# interconnect-board.net
KiCad netlist of a schematic drawn in EAGLE
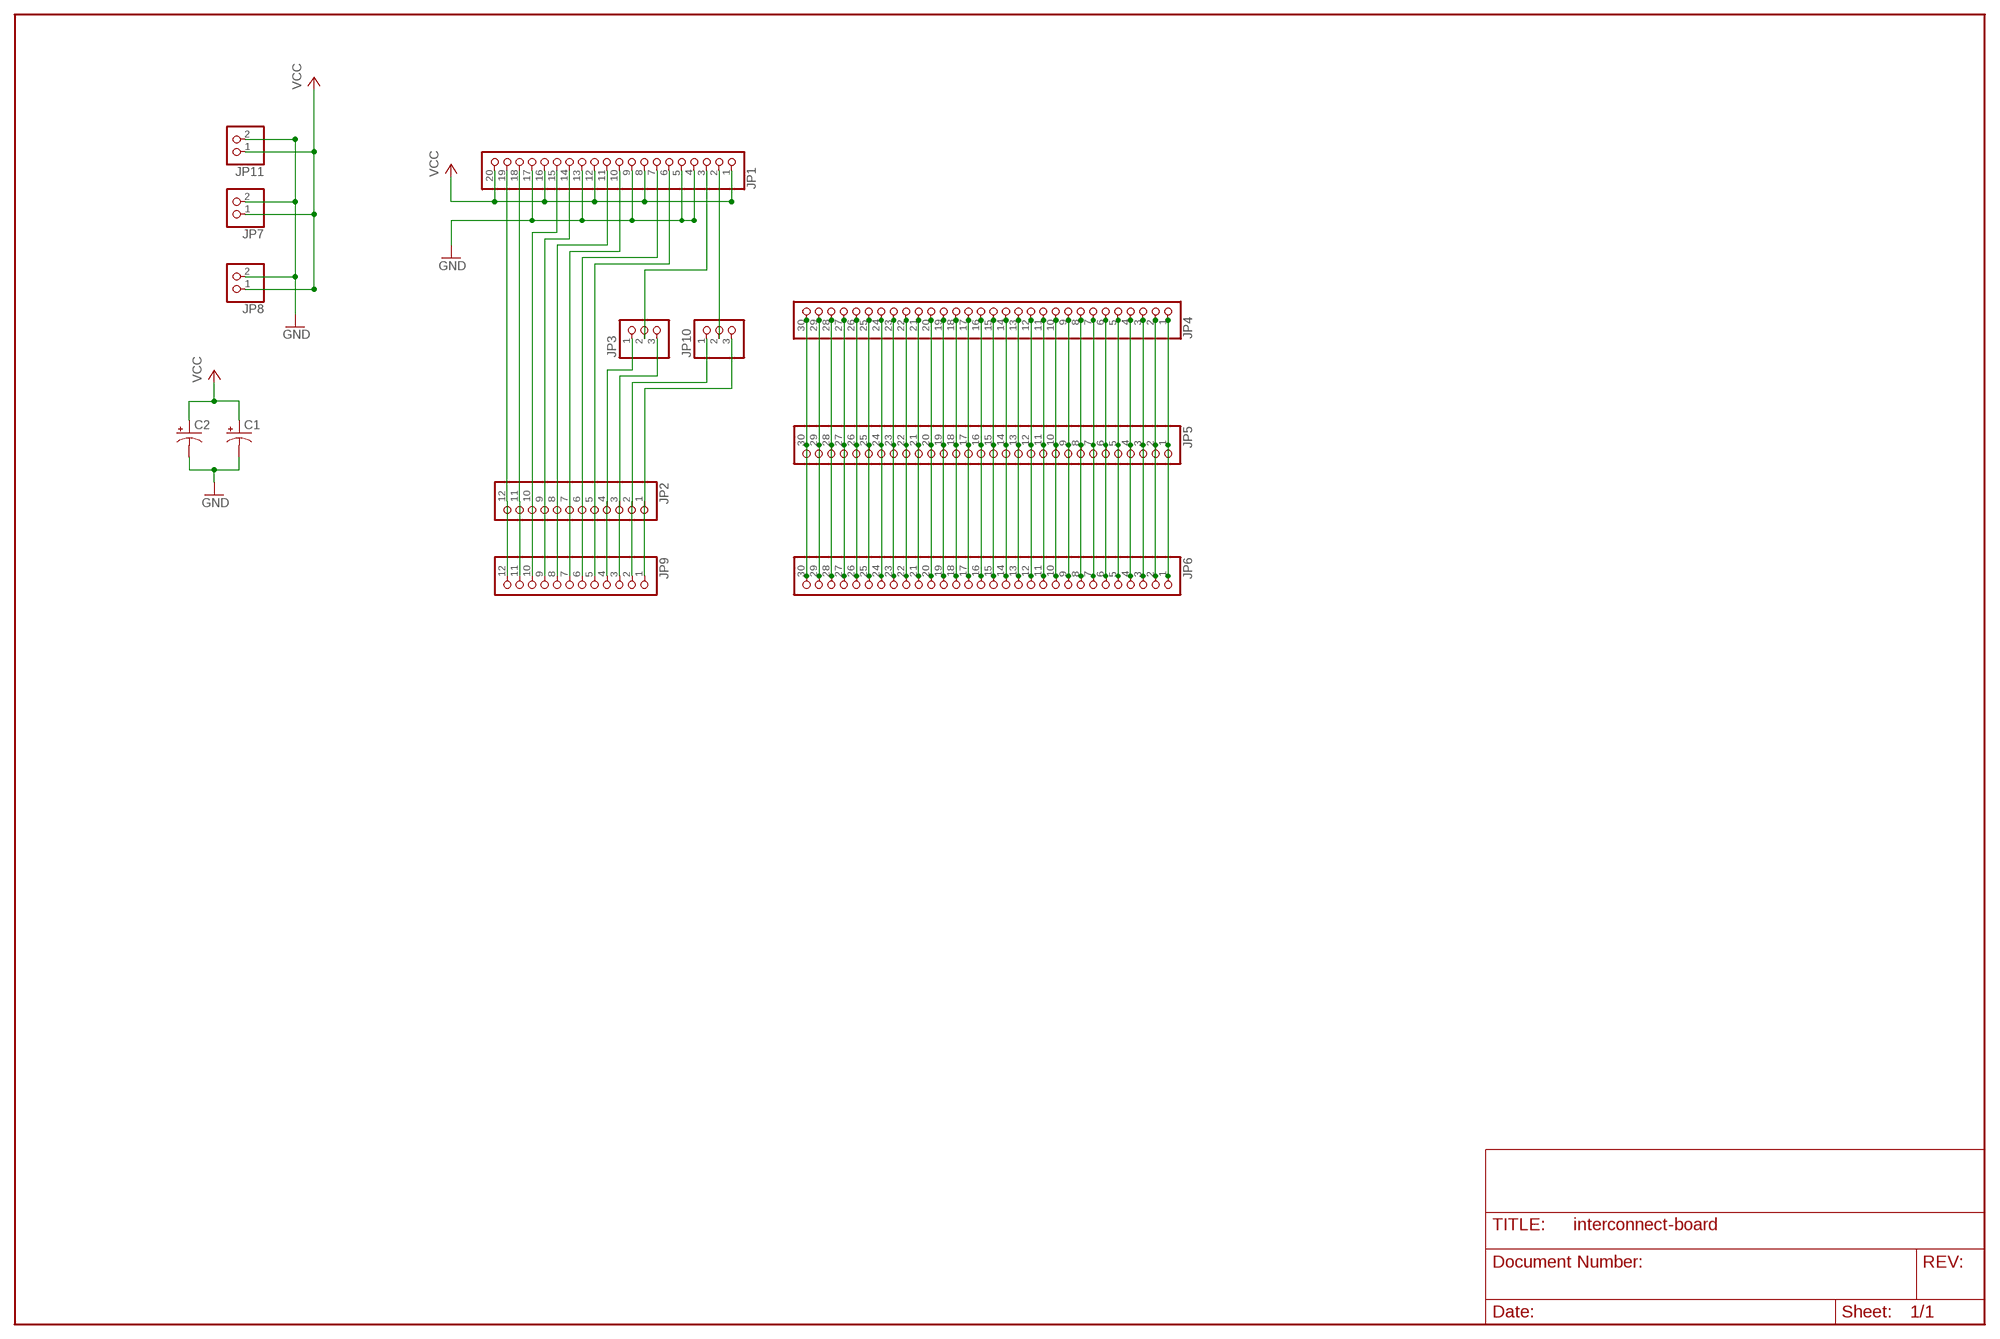
[diagram p0: schematic, sheet 1]

(export (version "E")
  (design (tool "Eeschema 10.0.6"))
  (components
    (comp (ref "C1")
      (value "CPOL-USE15-6AXIAL")
      (footprint "eagle-import:E15-6")
      (libsource (lib "eagle-import") (part "CPOL-USE15-6AXIAL"))
    )
    (comp (ref "C2")
      (value "CPOL-USE15-6AXIAL")
      (footprint "eagle-import:E15-6")
      (libsource (lib "eagle-import") (part "CPOL-USE15-6AXIAL"))
    )
    (comp (ref "JP1")
      (value "PINHD-1X20")
      (footprint "eagle-import:1X20")
      (libsource (lib "eagle-import") (part "PINHD-1X20"))
    )
    (comp (ref "JP2")
      (value "PINHD-1X12")
      (footprint "eagle-import:1X12")
      (libsource (lib "eagle-import") (part "PINHD-1X12"))
    )
    (comp (ref "JP3")
      (value "PINHD-1X3")
      (footprint "eagle-import:1X03")
      (libsource (lib "eagle-import") (part "PINHD-1X3"))
    )
    (comp (ref "JP4")
      (value "PINHD-1X30")
      (footprint "eagle-import:1X30")
      (libsource (lib "eagle-import") (part "PINHD-1X30"))
    )
    (comp (ref "JP5")
      (value "PINHD-1X30")
      (footprint "eagle-import:1X30")
      (libsource (lib "eagle-import") (part "PINHD-1X30"))
    )
    (comp (ref "JP6")
      (value "PINHD-1X30")
      (footprint "eagle-import:1X30")
      (libsource (lib "eagle-import") (part "PINHD-1X30"))
    )
    (comp (ref "JP7")
      (value "PINHD-1X2")
      (footprint "eagle-import:1X02")
      (libsource (lib "eagle-import") (part "PINHD-1X2"))
    )
    (comp (ref "JP8")
      (value "PINHD-1X2")
      (footprint "eagle-import:1X02")
      (libsource (lib "eagle-import") (part "PINHD-1X2"))
    )
    (comp (ref "JP9")
      (value "PINHD-1X12")
      (footprint "eagle-import:1X12")
      (libsource (lib "eagle-import") (part "PINHD-1X12"))
    )
    (comp (ref "JP10")
      (value "PINHD-1X3")
      (footprint "eagle-import:1X03")
      (libsource (lib "eagle-import") (part "PINHD-1X3"))
    )
    (comp (ref "JP11")
      (value "PINHD-1X2")
      (footprint "eagle-import:1X02")
      (libsource (lib "eagle-import") (part "PINHD-1X2"))
    )
  )
  (nets
    (net (code "1") (name "GND") (class "Default")
      (node (ref "C1") (pin "-") (pinfunction "-_-") (pintype "passive"))
      (node (ref "C2") (pin "-") (pinfunction "-_-") (pintype "passive"))
      (node (ref "JP1") (pin "13") (pinfunction "13_13") (pintype "passive"))
      (node (ref "JP1") (pin "17") (pinfunction "17_17") (pintype "passive"))
      (node (ref "JP1") (pin "4") (pinfunction "4_4") (pintype "passive"))
      (node (ref "JP1") (pin "5") (pinfunction "5_5") (pintype "passive"))
      (node (ref "JP1") (pin "9") (pinfunction "9_9") (pintype "passive"))
      (node (ref "JP11") (pin "2") (pinfunction "2_2") (pintype "passive"))
      (node (ref "JP7") (pin "2") (pinfunction "2_2") (pintype "passive"))
      (node (ref "JP8") (pin "2") (pinfunction "2_2") (pintype "passive"))
    )
    (net (code "2") (name "Net-(JP1-Pad2)") (class "Default")
      (node (ref "JP1") (pin "2") (pinfunction "2_2") (pintype "passive"))
      (node (ref "JP10") (pin "2") (pinfunction "2_2") (pintype "passive"))
    )
    (net (code "3") (name "Net-(JP1-Pad3)") (class "Default")
      (node (ref "JP1") (pin "3") (pinfunction "3_3") (pintype "passive"))
      (node (ref "JP3") (pin "2") (pinfunction "2_2") (pintype "passive"))
    )
    (net (code "4") (name "Net-(JP1-Pad6)") (class "Default")
      (node (ref "JP1") (pin "6") (pinfunction "6_6") (pintype "passive"))
      (node (ref "JP2") (pin "5") (pinfunction "5_5") (pintype "passive"))
      (node (ref "JP9") (pin "5") (pinfunction "5_5") (pintype "passive"))
    )
    (net (code "5") (name "Net-(JP1-Pad7)") (class "Default")
      (node (ref "JP1") (pin "7") (pinfunction "7_7") (pintype "passive"))
      (node (ref "JP2") (pin "6") (pinfunction "6_6") (pintype "passive"))
      (node (ref "JP9") (pin "6") (pinfunction "6_6") (pintype "passive"))
    )
    (net (code "6") (name "Net-(JP1-Pad10)") (class "Default")
      (node (ref "JP1") (pin "10") (pinfunction "10_10") (pintype "passive"))
      (node (ref "JP2") (pin "7") (pinfunction "7_7") (pintype "passive"))
      (node (ref "JP9") (pin "7") (pinfunction "7_7") (pintype "passive"))
    )
    (net (code "7") (name "Net-(JP1-Pad11)") (class "Default")
      (node (ref "JP1") (pin "11") (pinfunction "11_11") (pintype "passive"))
      (node (ref "JP2") (pin "8") (pinfunction "8_8") (pintype "passive"))
      (node (ref "JP9") (pin "8") (pinfunction "8_8") (pintype "passive"))
    )
    (net (code "8") (name "Net-(JP1-Pad14)") (class "Default")
      (node (ref "JP1") (pin "14") (pinfunction "14_14") (pintype "passive"))
      (node (ref "JP2") (pin "9") (pinfunction "9_9") (pintype "passive"))
      (node (ref "JP9") (pin "9") (pinfunction "9_9") (pintype "passive"))
    )
    (net (code "9") (name "Net-(JP1-Pad15)") (class "Default")
      (node (ref "JP1") (pin "15") (pinfunction "15_15") (pintype "passive"))
      (node (ref "JP2") (pin "10") (pinfunction "10_10") (pintype "passive"))
      (node (ref "JP9") (pin "10") (pinfunction "10_10") (pintype "passive"))
    )
    (net (code "10") (name "Net-(JP1-Pad18)") (class "Default")
      (node (ref "JP1") (pin "18") (pinfunction "18_18") (pintype "passive"))
      (node (ref "JP2") (pin "11") (pinfunction "11_11") (pintype "passive"))
      (node (ref "JP9") (pin "11") (pinfunction "11_11") (pintype "passive"))
    )
    (net (code "11") (name "Net-(JP1-Pad19)") (class "Default")
      (node (ref "JP1") (pin "19") (pinfunction "19_19") (pintype "passive"))
      (node (ref "JP2") (pin "12") (pinfunction "12_12") (pintype "passive"))
      (node (ref "JP9") (pin "12") (pinfunction "12_12") (pintype "passive"))
    )
    (net (code "12") (name "Net-(JP2-Pad3)") (class "Default")
      (node (ref "JP2") (pin "3") (pinfunction "3_3") (pintype "passive"))
      (node (ref "JP3") (pin "3") (pinfunction "3_3") (pintype "passive"))
      (node (ref "JP9") (pin "3") (pinfunction "3_3") (pintype "passive"))
    )
    (net (code "13") (name "Net-(JP2-Pad4)") (class "Default")
      (node (ref "JP2") (pin "4") (pinfunction "4_4") (pintype "passive"))
      (node (ref "JP3") (pin "1") (pinfunction "1_1") (pintype "passive"))
      (node (ref "JP9") (pin "4") (pinfunction "4_4") (pintype "passive"))
    )
    (net (code "14") (name "Net-(JP4-Pad1)") (class "Default")
      (node (ref "JP4") (pin "1") (pinfunction "1_1") (pintype "passive"))
      (node (ref "JP5") (pin "1") (pinfunction "1_1") (pintype "passive"))
      (node (ref "JP6") (pin "1") (pinfunction "1_1") (pintype "passive"))
    )
    (net (code "15") (name "Net-(JP4-Pad2)") (class "Default")
      (node (ref "JP4") (pin "2") (pinfunction "2_2") (pintype "passive"))
      (node (ref "JP5") (pin "2") (pinfunction "2_2") (pintype "passive"))
      (node (ref "JP6") (pin "2") (pinfunction "2_2") (pintype "passive"))
    )
    (net (code "16") (name "Net-(JP4-Pad3)") (class "Default")
      (node (ref "JP4") (pin "3") (pinfunction "3_3") (pintype "passive"))
      (node (ref "JP5") (pin "3") (pinfunction "3_3") (pintype "passive"))
      (node (ref "JP6") (pin "3") (pinfunction "3_3") (pintype "passive"))
    )
    (net (code "17") (name "Net-(JP4-Pad4)") (class "Default")
      (node (ref "JP4") (pin "4") (pinfunction "4_4") (pintype "passive"))
      (node (ref "JP5") (pin "4") (pinfunction "4_4") (pintype "passive"))
      (node (ref "JP6") (pin "4") (pinfunction "4_4") (pintype "passive"))
    )
    (net (code "18") (name "Net-(JP4-Pad5)") (class "Default")
      (node (ref "JP4") (pin "5") (pinfunction "5_5") (pintype "passive"))
      (node (ref "JP5") (pin "5") (pinfunction "5_5") (pintype "passive"))
      (node (ref "JP6") (pin "5") (pinfunction "5_5") (pintype "passive"))
    )
    (net (code "19") (name "Net-(JP4-Pad6)") (class "Default")
      (node (ref "JP4") (pin "6") (pinfunction "6_6") (pintype "passive"))
      (node (ref "JP5") (pin "6") (pinfunction "6_6") (pintype "passive"))
      (node (ref "JP6") (pin "6") (pinfunction "6_6") (pintype "passive"))
    )
    (net (code "20") (name "Net-(JP4-Pad7)") (class "Default")
      (node (ref "JP4") (pin "7") (pinfunction "7_7") (pintype "passive"))
      (node (ref "JP5") (pin "7") (pinfunction "7_7") (pintype "passive"))
      (node (ref "JP6") (pin "7") (pinfunction "7_7") (pintype "passive"))
    )
    (net (code "21") (name "Net-(JP4-Pad8)") (class "Default")
      (node (ref "JP4") (pin "8") (pinfunction "8_8") (pintype "passive"))
      (node (ref "JP5") (pin "8") (pinfunction "8_8") (pintype "passive"))
      (node (ref "JP6") (pin "8") (pinfunction "8_8") (pintype "passive"))
    )
    (net (code "22") (name "Net-(JP4-Pad9)") (class "Default")
      (node (ref "JP4") (pin "9") (pinfunction "9_9") (pintype "passive"))
      (node (ref "JP5") (pin "9") (pinfunction "9_9") (pintype "passive"))
      (node (ref "JP6") (pin "9") (pinfunction "9_9") (pintype "passive"))
    )
    (net (code "23") (name "Net-(JP4-Pad10)") (class "Default")
      (node (ref "JP4") (pin "10") (pinfunction "10_10") (pintype "passive"))
      (node (ref "JP5") (pin "10") (pinfunction "10_10") (pintype "passive"))
      (node (ref "JP6") (pin "10") (pinfunction "10_10") (pintype "passive"))
    )
    (net (code "24") (name "Net-(JP4-Pad11)") (class "Default")
      (node (ref "JP4") (pin "11") (pinfunction "11_11") (pintype "passive"))
      (node (ref "JP5") (pin "11") (pinfunction "11_11") (pintype "passive"))
      (node (ref "JP6") (pin "11") (pinfunction "11_11") (pintype "passive"))
    )
    (net (code "25") (name "Net-(JP4-Pad12)") (class "Default")
      (node (ref "JP4") (pin "12") (pinfunction "12_12") (pintype "passive"))
      (node (ref "JP5") (pin "12") (pinfunction "12_12") (pintype "passive"))
      (node (ref "JP6") (pin "12") (pinfunction "12_12") (pintype "passive"))
    )
    (net (code "26") (name "Net-(JP4-Pad13)") (class "Default")
      (node (ref "JP4") (pin "13") (pinfunction "13_13") (pintype "passive"))
      (node (ref "JP5") (pin "13") (pinfunction "13_13") (pintype "passive"))
      (node (ref "JP6") (pin "13") (pinfunction "13_13") (pintype "passive"))
    )
    (net (code "27") (name "Net-(JP4-Pad14)") (class "Default")
      (node (ref "JP4") (pin "14") (pinfunction "14_14") (pintype "passive"))
      (node (ref "JP5") (pin "14") (pinfunction "14_14") (pintype "passive"))
      (node (ref "JP6") (pin "14") (pinfunction "14_14") (pintype "passive"))
    )
    (net (code "28") (name "Net-(JP4-Pad15)") (class "Default")
      (node (ref "JP4") (pin "15") (pinfunction "15_15") (pintype "passive"))
      (node (ref "JP5") (pin "15") (pinfunction "15_15") (pintype "passive"))
      (node (ref "JP6") (pin "15") (pinfunction "15_15") (pintype "passive"))
    )
    (net (code "29") (name "Net-(JP4-Pad16)") (class "Default")
      (node (ref "JP4") (pin "16") (pinfunction "16_16") (pintype "passive"))
      (node (ref "JP5") (pin "16") (pinfunction "16_16") (pintype "passive"))
      (node (ref "JP6") (pin "16") (pinfunction "16_16") (pintype "passive"))
    )
    (net (code "30") (name "Net-(JP4-Pad17)") (class "Default")
      (node (ref "JP4") (pin "17") (pinfunction "17_17") (pintype "passive"))
      (node (ref "JP5") (pin "17") (pinfunction "17_17") (pintype "passive"))
      (node (ref "JP6") (pin "17") (pinfunction "17_17") (pintype "passive"))
    )
    (net (code "31") (name "Net-(JP4-Pad18)") (class "Default")
      (node (ref "JP4") (pin "18") (pinfunction "18_18") (pintype "passive"))
      (node (ref "JP5") (pin "18") (pinfunction "18_18") (pintype "passive"))
      (node (ref "JP6") (pin "18") (pinfunction "18_18") (pintype "passive"))
    )
    (net (code "32") (name "Net-(JP4-Pad19)") (class "Default")
      (node (ref "JP4") (pin "19") (pinfunction "19_19") (pintype "passive"))
      (node (ref "JP5") (pin "19") (pinfunction "19_19") (pintype "passive"))
      (node (ref "JP6") (pin "19") (pinfunction "19_19") (pintype "passive"))
    )
    (net (code "33") (name "Net-(JP4-Pad20)") (class "Default")
      (node (ref "JP4") (pin "20") (pinfunction "20_20") (pintype "passive"))
      (node (ref "JP5") (pin "20") (pinfunction "20_20") (pintype "passive"))
      (node (ref "JP6") (pin "20") (pinfunction "20_20") (pintype "passive"))
    )
    (net (code "34") (name "Net-(JP4-Pad21)") (class "Default")
      (node (ref "JP4") (pin "21") (pinfunction "21_21") (pintype "passive"))
      (node (ref "JP5") (pin "21") (pinfunction "21_21") (pintype "passive"))
      (node (ref "JP6") (pin "21") (pinfunction "21_21") (pintype "passive"))
    )
    (net (code "35") (name "Net-(JP4-Pad22)") (class "Default")
      (node (ref "JP4") (pin "22") (pinfunction "22_22") (pintype "passive"))
      (node (ref "JP5") (pin "22") (pinfunction "22_22") (pintype "passive"))
      (node (ref "JP6") (pin "22") (pinfunction "22_22") (pintype "passive"))
    )
    (net (code "36") (name "Net-(JP4-Pad23)") (class "Default")
      (node (ref "JP4") (pin "23") (pinfunction "23_23") (pintype "passive"))
      (node (ref "JP5") (pin "23") (pinfunction "23_23") (pintype "passive"))
      (node (ref "JP6") (pin "23") (pinfunction "23_23") (pintype "passive"))
    )
    (net (code "37") (name "Net-(JP4-Pad24)") (class "Default")
      (node (ref "JP4") (pin "24") (pinfunction "24_24") (pintype "passive"))
      (node (ref "JP5") (pin "24") (pinfunction "24_24") (pintype "passive"))
      (node (ref "JP6") (pin "24") (pinfunction "24_24") (pintype "passive"))
    )
    (net (code "38") (name "Net-(JP4-Pad25)") (class "Default")
      (node (ref "JP4") (pin "25") (pinfunction "25_25") (pintype "passive"))
      (node (ref "JP5") (pin "25") (pinfunction "25_25") (pintype "passive"))
      (node (ref "JP6") (pin "25") (pinfunction "25_25") (pintype "passive"))
    )
    (net (code "39") (name "Net-(JP4-Pad26)") (class "Default")
      (node (ref "JP4") (pin "26") (pinfunction "26_26") (pintype "passive"))
      (node (ref "JP5") (pin "26") (pinfunction "26_26") (pintype "passive"))
      (node (ref "JP6") (pin "26") (pinfunction "26_26") (pintype "passive"))
    )
    (net (code "40") (name "Net-(JP4-Pad27)") (class "Default")
      (node (ref "JP4") (pin "27") (pinfunction "27_27") (pintype "passive"))
      (node (ref "JP5") (pin "27") (pinfunction "27_27") (pintype "passive"))
      (node (ref "JP6") (pin "27") (pinfunction "27_27") (pintype "passive"))
    )
    (net (code "41") (name "Net-(JP4-Pad28)") (class "Default")
      (node (ref "JP4") (pin "28") (pinfunction "28_28") (pintype "passive"))
      (node (ref "JP5") (pin "28") (pinfunction "28_28") (pintype "passive"))
      (node (ref "JP6") (pin "28") (pinfunction "28_28") (pintype "passive"))
    )
    (net (code "42") (name "Net-(JP4-Pad29)") (class "Default")
      (node (ref "JP4") (pin "29") (pinfunction "29_29") (pintype "passive"))
      (node (ref "JP5") (pin "29") (pinfunction "29_29") (pintype "passive"))
      (node (ref "JP6") (pin "29") (pinfunction "29_29") (pintype "passive"))
    )
    (net (code "43") (name "Net-(JP4-Pad30)") (class "Default")
      (node (ref "JP4") (pin "30") (pinfunction "30_30") (pintype "passive"))
      (node (ref "JP5") (pin "30") (pinfunction "30_30") (pintype "passive"))
      (node (ref "JP6") (pin "30") (pinfunction "30_30") (pintype "passive"))
    )
    (net (code "44") (name "Net-(JP10-Pad1)") (class "Default")
      (node (ref "JP10") (pin "1") (pinfunction "1_1") (pintype "passive"))
      (node (ref "JP2") (pin "2") (pinfunction "2_2") (pintype "passive"))
      (node (ref "JP9") (pin "2") (pinfunction "2_2") (pintype "passive"))
    )
    (net (code "45") (name "Net-(JP10-Pad3)") (class "Default")
      (node (ref "JP10") (pin "3") (pinfunction "3_3") (pintype "passive"))
      (node (ref "JP2") (pin "1") (pinfunction "1_1") (pintype "passive"))
      (node (ref "JP9") (pin "1") (pinfunction "1_1") (pintype "passive"))
    )
    (net (code "46") (name "VCC") (class "Default")
      (node (ref "C1") (pin "+") (pinfunction "+_+") (pintype "passive"))
      (node (ref "C2") (pin "+") (pinfunction "+_+") (pintype "passive"))
      (node (ref "JP1") (pin "1") (pinfunction "1_1") (pintype "passive"))
      (node (ref "JP1") (pin "12") (pinfunction "12_12") (pintype "passive"))
      (node (ref "JP1") (pin "16") (pinfunction "16_16") (pintype "passive"))
      (node (ref "JP1") (pin "20") (pinfunction "20_20") (pintype "passive"))
      (node (ref "JP1") (pin "8") (pinfunction "8_8") (pintype "passive"))
      (node (ref "JP11") (pin "1") (pinfunction "1_1") (pintype "passive"))
      (node (ref "JP7") (pin "1") (pinfunction "1_1") (pintype "passive"))
      (node (ref "JP8") (pin "1") (pinfunction "1_1") (pintype "passive"))
    )
  )
)
